# adapter.net
KiCad netlist of a schematic drawn in EAGLE
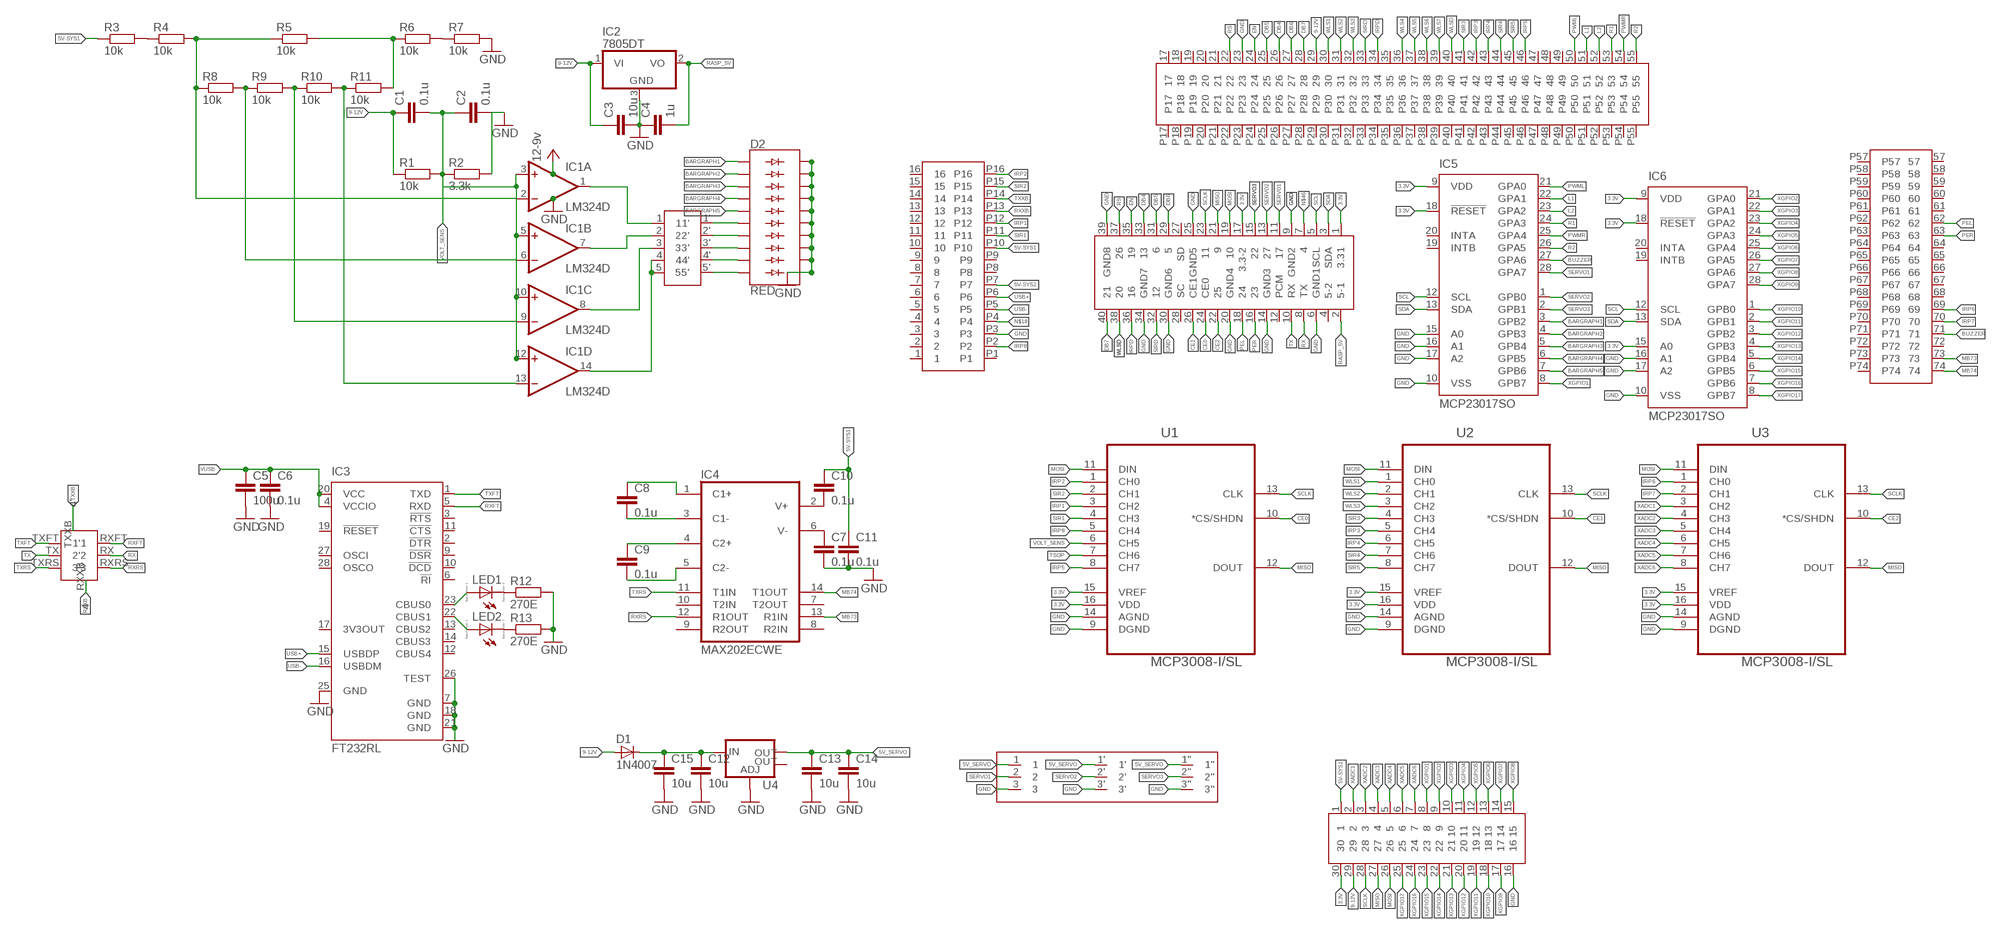
[diagram p0: schematic, sheet 1]

(export (version "E")
  (design (tool "Eeschema 10.0.6"))
  (components
    (comp (ref "C1")
      (value "0.1u")
      (footprint "eagle-import:C1206")
      (libsource (lib "eagle-import") (part "C-EUC1206"))
    )
    (comp (ref "C2")
      (value "0.1u")
      (footprint "eagle-import:C1206")
      (libsource (lib "eagle-import") (part "C-EUC1206"))
    )
    (comp (ref "C3")
      (value "10u")
      (footprint "eagle-import:C1206")
      (libsource (lib "eagle-import") (part "C-EUC1206"))
    )
    (comp (ref "C4")
      (value "1u")
      (footprint "eagle-import:C1206")
      (libsource (lib "eagle-import") (part "C-EUC1206"))
    )
    (comp (ref "C5")
      (value "100u")
      (footprint "eagle-import:C1206")
      (libsource (lib "eagle-import") (part "C-EUC1206"))
    )
    (comp (ref "C6")
      (value "0.1u")
      (footprint "eagle-import:C1206")
      (libsource (lib "eagle-import") (part "C-EUC1206"))
    )
    (comp (ref "C7")
      (value "0.1u")
      (footprint "eagle-import:C1206")
      (libsource (lib "eagle-import") (part "C-EUC1206"))
    )
    (comp (ref "C8")
      (value "0.1u")
      (footprint "eagle-import:C1206")
      (libsource (lib "eagle-import") (part "C-EUC1206"))
    )
    (comp (ref "C9")
      (value "0.1u")
      (footprint "eagle-import:C1206")
      (libsource (lib "eagle-import") (part "C-EUC1206"))
    )
    (comp (ref "C10")
      (value "0.1u")
      (footprint "eagle-import:C1206")
      (libsource (lib "eagle-import") (part "C-EUC1206"))
    )
    (comp (ref "C11")
      (value "0.1u")
      (footprint "eagle-import:C1206")
      (libsource (lib "eagle-import") (part "C-EUC1206"))
    )
    (comp (ref "C12")
      (value "10u")
      (footprint "eagle-import:C1206")
      (libsource (lib "eagle-import") (part "C-EUC1206"))
    )
    (comp (ref "C13")
      (value "10u")
      (footprint "eagle-import:C1206")
      (libsource (lib "eagle-import") (part "C-EUC1206"))
    )
    (comp (ref "C14")
      (value "10u")
      (footprint "eagle-import:C1206")
      (libsource (lib "eagle-import") (part "C-EUC1206"))
    )
    (comp (ref "C15")
      (value "10u")
      (footprint "eagle-import:C1206")
      (libsource (lib "eagle-import") (part "C-EUC1206"))
    )
    (comp (ref "D1")
      (value "1N4007")
      (footprint "eagle-import:SMA")
      (libsource (lib "eagle-import") (part "1N4007"))
    )
    (comp (ref "D2")
      (value "RED")
      (footprint "eagle-import:LED_BARGRAPH_10")
      (libsource (lib "eagle-import") (part "LED_BARGRAPH_10RED"))
    )
    (comp (ref "IC1")
      (value "LM324D")
      (footprint "eagle-import:SO14")
      (libsource (lib "eagle-import") (part "LM324D"))
    )
    (comp (ref "IC2")
      (value "7805DT")
      (footprint "eagle-import:TO252")
      (libsource (lib "eagle-import") (part "78DT05"))
    )
    (comp (ref "IC3")
      (value "FT232RL")
      (footprint "eagle-import:SSOP28")
      (libsource (lib "eagle-import") (part "FT232RL"))
    )
    (comp (ref "IC4")
      (value "MAX202ECWE")
      (footprint "eagle-import:SO16L")
      (fields (field (name "MPN") "MAX202ECWE+T"))
      (libsource (lib "eagle-import") (part "MAX202ECWE"))
    )
    (comp (ref "IC5")
      (value "MCP23017SO")
      (footprint "eagle-import:SO28W")
      (libsource (lib "eagle-import") (part "MCP23017SO"))
    )
    (comp (ref "IC6")
      (value "MCP23017SO")
      (footprint "eagle-import:SO28W")
      (libsource (lib "eagle-import") (part "MCP23017SO"))
    )
    (comp (ref "LED1")
      (value "LED_E")
      (footprint "eagle-import:LED_1206")
      (libsource (lib "eagle-import") (part "LED_E"))
    )
    (comp (ref "LED2")
      (value "LED_E")
      (footprint "eagle-import:LED_1206")
      (libsource (lib "eagle-import") (part "LED_E"))
    )
    (comp (ref "R1")
      (value "10k")
      (footprint "eagle-import:M1206")
      (libsource (lib "eagle-import") (part "R-EU_M1206"))
    )
    (comp (ref "R2")
      (value "3.3k")
      (footprint "eagle-import:M1206")
      (libsource (lib "eagle-import") (part "R-EU_M1206"))
    )
    (comp (ref "R3")
      (value "10k")
      (footprint "eagle-import:M1206")
      (libsource (lib "eagle-import") (part "R-EU_M1206"))
    )
    (comp (ref "R4")
      (value "10k")
      (footprint "eagle-import:M1206")
      (libsource (lib "eagle-import") (part "R-EU_M1206"))
    )
    (comp (ref "R5")
      (value "10k")
      (footprint "eagle-import:M1206")
      (libsource (lib "eagle-import") (part "R-EU_M1206"))
    )
    (comp (ref "R6")
      (value "10k")
      (footprint "eagle-import:M1206")
      (libsource (lib "eagle-import") (part "R-EU_M1206"))
    )
    (comp (ref "R7")
      (value "10k")
      (footprint "eagle-import:M1206")
      (libsource (lib "eagle-import") (part "R-EU_M1206"))
    )
    (comp (ref "R8")
      (value "10k")
      (footprint "eagle-import:M1206")
      (libsource (lib "eagle-import") (part "R-EU_M1206"))
    )
    (comp (ref "R9")
      (value "10k")
      (footprint "eagle-import:M1206")
      (libsource (lib "eagle-import") (part "R-EU_M1206"))
    )
    (comp (ref "R10")
      (value "10k")
      (footprint "eagle-import:M1206")
      (libsource (lib "eagle-import") (part "R-EU_M1206"))
    )
    (comp (ref "R11")
      (value "10k")
      (footprint "eagle-import:M1206")
      (libsource (lib "eagle-import") (part "R-EU_M1206"))
    )
    (comp (ref "R12")
      (value "270E")
      (footprint "eagle-import:R1206")
      (libsource (lib "eagle-import") (part "R-EU_R1206"))
    )
    (comp (ref "R13")
      (value "270E")
      (footprint "eagle-import:R1206")
      (libsource (lib "eagle-import") (part "R-EU_R1206"))
    )
    (comp (ref "U$1")
      (value "BOARD")
      (footprint "eagle-import:FEMHEADER")
      (libsource (lib "eagle-import") (part "BOARD"))
    )
    (comp (ref "U$2")
      (value "MALE_HEADER")
      (footprint "eagle-import:MALE_HEADER_PACKAGE")
      (libsource (lib "eagle-import") (part "MALE_HEADER"))
    )
    (comp (ref "U$3")
      (value "SWITCH_RXTX")
      (footprint "eagle-import:SWITCH_RXTX")
      (libsource (lib "eagle-import") (part "SWITCH_RXTX"))
    )
    (comp (ref "U$4")
      (value "SWITCH5")
      (footprint "eagle-import:SWITCH5")
      (libsource (lib "eagle-import") (part "SWITCH5"))
    )
    (comp (ref "U$5")
      (value "PORT_EXP")
      (footprint "eagle-import:PORT_EXP")
      (libsource (lib "eagle-import") (part "PORT_EXP"))
    )
    (comp (ref "U$7")
      (value "SERVO")
      (footprint "eagle-import:SERVO")
      (libsource (lib "eagle-import") (part "SERVO"))
    )
    (comp (ref "U1")
      (value "MCP3008-I/SL")
      (footprint "eagle-import:SOIC127P600X175-16N")
      (fields (field (name "MF") "Microchip"))
      (libsource (lib "eagle-import") (part "MCP3008-I/SL"))
    )
    (comp (ref "U2")
      (value "MCP3008-I/SL")
      (footprint "eagle-import:SOIC127P600X175-16N")
      (fields (field (name "MF") "Microchip"))
      (libsource (lib "eagle-import") (part "MCP3008-I/SL"))
    )
    (comp (ref "U3")
      (value "MCP3008-I/SL")
      (footprint "eagle-import:SOIC127P600X175-16N")
      (fields (field (name "MF") "Microchip"))
      (libsource (lib "eagle-import") (part "MCP3008-I/SL"))
    )
    (comp (ref "U4")
      (value "V_REG_LM1117SOT223")
      (footprint "eagle-import:SOT223")
      (libsource (lib "eagle-import") (part "V_REG_LM1117SOT223"))
    )
  )
  (nets
    (net (code "1") (name "3.3V") (class "Default")
      (node (ref "IC5") (pin "18") (pinfunction "~{RESET}_18") (pintype "input"))
      (node (ref "IC5") (pin "9") (pinfunction "VDD_9") (pintype "power_in"))
      (node (ref "IC6") (pin "15") (pinfunction "A0_15") (pintype "input"))
      (node (ref "IC6") (pin "18") (pinfunction "~{RESET}_18") (pintype "input"))
      (node (ref "IC6") (pin "9") (pinfunction "VDD_9") (pintype "power_in"))
      (node (ref "U$2") (pin "1") (pinfunction "3.31_1") (pintype "bidirectional"))
      (node (ref "U$2") (pin "17") (pinfunction "3.3-2_17") (pintype "bidirectional"))
      (node (ref "U$5") (pin "30") (pinfunction "30_30") (pintype "bidirectional"))
      (node (ref "U1") (pin "15") (pinfunction "VREF_15") (pintype "input"))
      (node (ref "U1") (pin "16") (pinfunction "VDD_16") (pintype "power_in"))
      (node (ref "U2") (pin "15") (pinfunction "VREF_15") (pintype "input"))
      (node (ref "U2") (pin "16") (pinfunction "VDD_16") (pintype "power_in"))
      (node (ref "U3") (pin "15") (pinfunction "VREF_15") (pintype "input"))
      (node (ref "U3") (pin "16") (pinfunction "VDD_16") (pintype "power_in"))
    )
    (net (code "2") (name "5V-SYS1") (class "Default")
      (node (ref "C10") (pin "1") (pinfunction "1_1") (pintype "passive"))
      (node (ref "C11") (pin "1") (pinfunction "1_1") (pintype "passive"))
      (node (ref "R3") (pin "1") (pinfunction "1_1") (pintype "passive"))
      (node (ref "U$1") (pin "P10") (pinfunction "P10_P10") (pintype "bidirectional"))
      (node (ref "U$5") (pin "1") (pinfunction "1_1") (pintype "bidirectional"))
    )
    (net (code "3") (name "5V-SYS2") (class "Default")
      (node (ref "U$1") (pin "P7") (pinfunction "P7_P7") (pintype "bidirectional"))
    )
    (net (code "4") (name "5V_SERVO") (class "Default")
      (node (ref "C13") (pin "1") (pinfunction "1_1") (pintype "passive"))
      (node (ref "C14") (pin "1") (pinfunction "1_1") (pintype "passive"))
      (node (ref "U$7") (pin "1") (pinfunction "1_1") (pintype "bidirectional"))
      (node (ref "U$7") (pin "1\"") (pinfunction "1\"_1\"") (pintype "bidirectional"))
      (node (ref "U$7") (pin "1'") (pinfunction "1'_1'") (pintype "bidirectional"))
      (node (ref "U4") (pin "2") (pinfunction "OUT_2") (pintype "output"))
    )
    (net (code "5") (name "9-12V") (class "Default")
      (node (ref "C1") (pin "1") (pinfunction "1_1") (pintype "passive"))
      (node (ref "C3") (pin "1") (pinfunction "1_1") (pintype "passive"))
      (node (ref "D1") (pin "A") (pinfunction "A_A") (pintype "passive"))
      (node (ref "IC2") (pin "1") (pinfunction "VI_1") (pintype "input"))
      (node (ref "R1") (pin "1") (pinfunction "1_1") (pintype "passive"))
      (node (ref "U$1") (pin "29") (pinfunction "29_29") (pintype "bidirectional"))
      (node (ref "U$5") (pin "29") (pinfunction "29_29") (pintype "bidirectional"))
    )
    (net (code "7") (name "BARGRAPH1") (class "Default")
      (node (ref "D2") (pin "1") (pinfunction "A_1") (pintype "passive"))
      (node (ref "IC5") (pin "3") (pinfunction "GPB2_3") (pintype "bidirectional"))
    )
    (net (code "8") (name "BARGRAPH2") (class "Default")
      (node (ref "D2") (pin "2") (pinfunction "A1_2") (pintype "passive"))
      (node (ref "IC5") (pin "4") (pinfunction "GPB3_4") (pintype "bidirectional"))
    )
    (net (code "9") (name "BARGRAPH3") (class "Default")
      (node (ref "D2") (pin "3") (pinfunction "A2_3") (pintype "passive"))
      (node (ref "IC5") (pin "5") (pinfunction "GPB4_5") (pintype "bidirectional"))
    )
    (net (code "10") (name "BARGRAPH4") (class "Default")
      (node (ref "D2") (pin "4") (pinfunction "A3_4") (pintype "passive"))
      (node (ref "IC5") (pin "6") (pinfunction "GPB5_6") (pintype "bidirectional"))
    )
    (net (code "11") (name "BARGRAPH5") (class "Default")
      (node (ref "D2") (pin "5") (pinfunction "A4_5") (pintype "passive"))
      (node (ref "IC5") (pin "7") (pinfunction "GPB6_7") (pintype "bidirectional"))
    )
    (net (code "12") (name "BUZZER") (class "Default")
      (node (ref "IC5") (pin "27") (pinfunction "GPA6_27") (pintype "bidirectional"))
      (node (ref "U$1") (pin "71") (pinfunction "71_71") (pintype "bidirectional"))
    )
    (net (code "13") (name "CE0") (class "Default")
      (node (ref "U$2") (pin "24") (pinfunction "CE0_24") (pintype "bidirectional"))
      (node (ref "U1") (pin "10") (pinfunction "*CS/SHDN_10") (pintype "input"))
    )
    (net (code "14") (name "CE1") (class "Default")
      (node (ref "U$2") (pin "26") (pinfunction "CE1_26") (pintype "bidirectional"))
      (node (ref "U2") (pin "10") (pinfunction "*CS/SHDN_10") (pintype "input"))
    )
    (net (code "15") (name "CE2") (class "Default")
      (node (ref "U$2") (pin "22") (pinfunction "25_22") (pintype "bidirectional"))
      (node (ref "U3") (pin "10") (pinfunction "*CS/SHDN_10") (pintype "input"))
    )
    (net (code "16") (name "DB4") (class "Default")
      (node (ref "U$1") (pin "26") (pinfunction "26_26") (pintype "bidirectional"))
      (node (ref "U$2") (pin "33") (pinfunction "13_33") (pintype "bidirectional"))
    )
    (net (code "17") (name "DB5") (class "Default")
      (node (ref "U$1") (pin "25") (pinfunction "25_25") (pintype "bidirectional"))
      (node (ref "U$2") (pin "31") (pinfunction "6_31") (pintype "bidirectional"))
    )
    (net (code "18") (name "DB6") (class "Default")
      (node (ref "U$1") (pin "27") (pinfunction "27_27") (pintype "bidirectional"))
      (node (ref "U$2") (pin "29") (pinfunction "5_29") (pintype "bidirectional"))
    )
    (net (code "19") (name "DB7") (class "Default")
      (node (ref "U$1") (pin "28") (pinfunction "28_28") (pintype "bidirectional"))
      (node (ref "U$2") (pin "40") (pinfunction "21_40") (pintype "bidirectional"))
    )
    (net (code "20") (name "EN") (class "Default")
      (node (ref "U$1") (pin "24") (pinfunction "24_24") (pintype "bidirectional"))
      (node (ref "U$2") (pin "35") (pinfunction "19_35") (pintype "bidirectional"))
    )
    (net (code "21") (name "GND") (class "Default")
      (node (ref "C11") (pin "2") (pinfunction "2_2") (pintype "passive"))
      (node (ref "C12") (pin "2") (pinfunction "2_2") (pintype "passive"))
      (node (ref "C13") (pin "2") (pinfunction "2_2") (pintype "passive"))
      (node (ref "C14") (pin "2") (pinfunction "2_2") (pintype "passive"))
      (node (ref "C15") (pin "2") (pinfunction "2_2") (pintype "passive"))
      (node (ref "C2") (pin "2") (pinfunction "2_2") (pintype "passive"))
      (node (ref "C3") (pin "2") (pinfunction "2_2") (pintype "passive"))
      (node (ref "C4") (pin "1") (pinfunction "1_1") (pintype "passive"))
      (node (ref "C5") (pin "2") (pinfunction "2_2") (pintype "passive"))
      (node (ref "C6") (pin "2") (pinfunction "2_2") (pintype "passive"))
      (node (ref "C7") (pin "2") (pinfunction "2_2") (pintype "passive"))
      (node (ref "D2") (pin "11") (pinfunction "C9_11") (pintype "passive"))
      (node (ref "D2") (pin "12") (pinfunction "C8_12") (pintype "passive"))
      (node (ref "D2") (pin "13") (pinfunction "C7_13") (pintype "passive"))
      (node (ref "D2") (pin "14") (pinfunction "C6_14") (pintype "passive"))
      (node (ref "D2") (pin "15") (pinfunction "C5_15") (pintype "passive"))
      (node (ref "D2") (pin "16") (pinfunction "C4_16") (pintype "passive"))
      (node (ref "D2") (pin "17") (pinfunction "C3_17") (pintype "passive"))
      (node (ref "D2") (pin "18") (pinfunction "C2_18") (pintype "passive"))
      (node (ref "D2") (pin "19") (pinfunction "C1_19") (pintype "passive"))
      (node (ref "D2") (pin "20") (pinfunction "C_20") (pintype "passive"))
      (node (ref "IC2") (pin "3") (pinfunction "GND_3") (pintype "passive"))
      (node (ref "IC3") (pin "18") (pinfunction "GND_18") (pintype "power_in"))
      (node (ref "IC3") (pin "21") (pinfunction "GND_21") (pintype "power_in"))
      (node (ref "IC3") (pin "25") (pinfunction "GND_25") (pintype "power_in"))
      (node (ref "IC3") (pin "26") (pinfunction "TEST_26") (pintype "input"))
      (node (ref "IC3") (pin "7") (pinfunction "GND_7") (pintype "power_in"))
      (node (ref "IC5") (pin "10") (pinfunction "VSS_10") (pintype "power_in"))
      (node (ref "IC5") (pin "15") (pinfunction "A0_15") (pintype "input"))
      (node (ref "IC5") (pin "16") (pinfunction "A1_16") (pintype "input"))
      (node (ref "IC5") (pin "17") (pinfunction "A2_17") (pintype "input"))
      (node (ref "IC6") (pin "10") (pinfunction "VSS_10") (pintype "power_in"))
      (node (ref "IC6") (pin "16") (pinfunction "A1_16") (pintype "input"))
      (node (ref "IC6") (pin "17") (pinfunction "A2_17") (pintype "input"))
      (node (ref "R12") (pin "2") (pinfunction "2_2") (pintype "passive"))
      (node (ref "R13") (pin "2") (pinfunction "2_2") (pintype "passive"))
      (node (ref "R2") (pin "2") (pinfunction "2_2") (pintype "passive"))
      (node (ref "R7") (pin "2") (pinfunction "2_2") (pintype "passive"))
      (node (ref "U$1") (pin "23") (pinfunction "23_23") (pintype "bidirectional"))
      (node (ref "U$1") (pin "P3") (pinfunction "P3_P3") (pintype "bidirectional"))
      (node (ref "U$2") (pin "14") (pinfunction "GND3_14") (pintype "bidirectional"))
      (node (ref "U$2") (pin "20") (pinfunction "GND4_20") (pintype "bidirectional"))
      (node (ref "U$2") (pin "25") (pinfunction "GND5_25") (pintype "bidirectional"))
      (node (ref "U$2") (pin "30") (pinfunction "GND6_30") (pintype "bidirectional"))
      (node (ref "U$2") (pin "34") (pinfunction "GND7_34") (pintype "bidirectional"))
      (node (ref "U$2") (pin "39") (pinfunction "GND8_39") (pintype "bidirectional"))
      (node (ref "U$2") (pin "6") (pinfunction "GND1_6") (pintype "bidirectional"))
      (node (ref "U$2") (pin "9") (pinfunction "GND2_9") (pintype "bidirectional"))
      (node (ref "U$5") (pin "16") (pinfunction "16_16") (pintype "bidirectional"))
      (node (ref "U$7") (pin "3") (pinfunction "3_3") (pintype "bidirectional"))
      (node (ref "U$7") (pin "3\"") (pinfunction "3\"_3\"") (pintype "bidirectional"))
      (node (ref "U$7") (pin "3'") (pinfunction "3'_3'") (pintype "bidirectional"))
      (node (ref "U1") (pin "14") (pinfunction "AGND_14") (pintype "passive"))
      (node (ref "U1") (pin "9") (pinfunction "DGND_9") (pintype "passive"))
      (node (ref "U2") (pin "14") (pinfunction "AGND_14") (pintype "passive"))
      (node (ref "U2") (pin "9") (pinfunction "DGND_9") (pintype "passive"))
      (node (ref "U3") (pin "14") (pinfunction "AGND_14") (pintype "passive"))
      (node (ref "U3") (pin "9") (pinfunction "DGND_9") (pintype "passive"))
      (node (ref "U4") (pin "1") (pinfunction "ADJ_1") (pintype "input"))
    )
    (net (code "22") (name "IRP1") (class "Default")
      (node (ref "U$1") (pin "P12") (pinfunction "P12_P12") (pintype "bidirectional"))
      (node (ref "U1") (pin "3") (pinfunction "CH2_3") (pintype "input"))
    )
    (net (code "23") (name "IRP2") (class "Default")
      (node (ref "U$1") (pin "P16") (pinfunction "P16_P16") (pintype "bidirectional"))
      (node (ref "U1") (pin "1") (pinfunction "CH0_1") (pintype "input"))
    )
    (net (code "24") (name "IRP3") (class "Default")
      (node (ref "U$1") (pin "42") (pinfunction "42_42") (pintype "bidirectional"))
      (node (ref "U2") (pin "5") (pinfunction "CH4_5") (pintype "input"))
    )
    (net (code "25") (name "IRP4") (class "Default")
      (node (ref "U$1") (pin "43") (pinfunction "43_43") (pintype "bidirectional"))
      (node (ref "U2") (pin "6") (pinfunction "CH5_6") (pintype "input"))
    )
    (net (code "26") (name "IRP5") (class "Default")
      (node (ref "U$1") (pin "46") (pinfunction "46_46") (pintype "bidirectional"))
      (node (ref "U1") (pin "8") (pinfunction "CH7_8") (pintype "input"))
    )
    (net (code "27") (name "IRP6") (class "Default")
      (node (ref "U$1") (pin "69") (pinfunction "69_69") (pintype "bidirectional"))
      (node (ref "U3") (pin "1") (pinfunction "CH0_1") (pintype "input"))
    )
    (net (code "28") (name "IRP7") (class "Default")
      (node (ref "U$1") (pin "70") (pinfunction "70_70") (pintype "bidirectional"))
      (node (ref "U3") (pin "2") (pinfunction "CH1_2") (pintype "input"))
    )
    (net (code "29") (name "IRP8") (class "Default")
      (node (ref "U$1") (pin "P2") (pinfunction "P2_P2") (pintype "bidirectional"))
      (node (ref "U1") (pin "5") (pinfunction "CH4_5") (pintype "input"))
    )
    (net (code "30") (name "IRPD") (class "Default")
      (node (ref "U$1") (pin "34") (pinfunction "34_34") (pintype "bidirectional"))
      (node (ref "U$2") (pin "36") (pinfunction "16_36") (pintype "bidirectional"))
    )
    (net (code "31") (name "L1") (class "Default")
      (node (ref "IC5") (pin "22") (pinfunction "GPA1_22") (pintype "bidirectional"))
      (node (ref "U$1") (pin "51") (pinfunction "51_51") (pintype "bidirectional"))
    )
    (net (code "32") (name "L2") (class "Default")
      (node (ref "IC5") (pin "23") (pinfunction "GPA2_23") (pintype "bidirectional"))
      (node (ref "U$1") (pin "52") (pinfunction "52_52") (pintype "bidirectional"))
    )
    (net (code "33") (name "MB73") (class "Default")
      (node (ref "IC4") (pin "13") (pinfunction "R1IN_13") (pintype "input"))
      (node (ref "U$1") (pin "73") (pinfunction "73_73") (pintype "bidirectional"))
    )
    (net (code "34") (name "MB74") (class "Default")
      (node (ref "IC4") (pin "14") (pinfunction "T1OUT_14") (pintype "output"))
      (node (ref "U$1") (pin "74") (pinfunction "74_74") (pintype "bidirectional"))
    )
    (net (code "35") (name "MISO") (class "Default")
      (node (ref "U$2") (pin "21") (pinfunction "9_21") (pintype "bidirectional"))
      (node (ref "U$5") (pin "27") (pinfunction "27_27") (pintype "bidirectional"))
      (node (ref "U1") (pin "12") (pinfunction "DOUT_12") (pintype "output"))
      (node (ref "U2") (pin "12") (pinfunction "DOUT_12") (pintype "output"))
      (node (ref "U3") (pin "12") (pinfunction "DOUT_12") (pintype "output"))
    )
    (net (code "36") (name "MOSI") (class "Default")
      (node (ref "U$2") (pin "19") (pinfunction "10_19") (pintype "bidirectional"))
      (node (ref "U$5") (pin "26") (pinfunction "26_26") (pintype "bidirectional"))
      (node (ref "U1") (pin "11") (pinfunction "DIN_11") (pintype "input"))
      (node (ref "U2") (pin "11") (pinfunction "DIN_11") (pintype "input"))
      (node (ref "U3") (pin "11") (pinfunction "DIN_11") (pintype "input"))
    )
    (net (code "37") (name "N$18") (class "Default")
      (node (ref "U$1") (pin "P4") (pinfunction "P4_P4") (pintype "bidirectional"))
    )
    (net (code "38") (name "N$46") (class "Default")
      (node (ref "U$2") (pin "7") (pinfunction "4_7") (pintype "bidirectional"))
    )
    (net (code "39") (name "Net-(D1-C)") (class "Default")
      (node (ref "C12") (pin "1") (pinfunction "1_1") (pintype "passive"))
      (node (ref "C15") (pin "1") (pinfunction "1_1") (pintype "passive"))
      (node (ref "D1") (pin "K") (pinfunction "C_K") (pintype "passive"))
      (node (ref "U4") (pin "3") (pinfunction "IN_3") (pintype "input"))
    )
    (net (code "40") (name "Net-(D2-A5)") (class "Default")
      (node (ref "D2") (pin "6") (pinfunction "A5_6") (pintype "passive"))
      (node (ref "U$4") (pin "1'") (pinfunction "1'_1'") (pintype "bidirectional"))
    )
    (net (code "41") (name "Net-(D2-A6)") (class "Default")
      (node (ref "D2") (pin "7") (pinfunction "A6_7") (pintype "passive"))
      (node (ref "U$4") (pin "2'") (pinfunction "2'_2'") (pintype "bidirectional"))
    )
    (net (code "42") (name "Net-(D2-A7)") (class "Default")
      (node (ref "D2") (pin "8") (pinfunction "A7_8") (pintype "passive"))
      (node (ref "U$4") (pin "3'") (pinfunction "3'_3'") (pintype "bidirectional"))
    )
    (net (code "43") (name "Net-(D2-A8)") (class "Default")
      (node (ref "D2") (pin "9") (pinfunction "A8_9") (pintype "passive"))
      (node (ref "U$4") (pin "4'") (pinfunction "4'_4'") (pintype "bidirectional"))
    )
    (net (code "44") (name "Net-(D2-A9)") (class "Default")
      (node (ref "D2") (pin "10") (pinfunction "A9_10") (pintype "passive"))
      (node (ref "U$4") (pin "5'") (pinfunction "5'_5'") (pintype "bidirectional"))
    )
    (net (code "45") (name "Net-(IC1A--IN)") (class "Default")
      (node (ref "IC1") (pin "2") (pinfunction "-IN_2") (pintype "input"))
      (node (ref "R4") (pin "2") (pinfunction "2_2") (pintype "passive"))
      (node (ref "R5") (pin "1") (pinfunction "1_1") (pintype "passive"))
      (node (ref "R8") (pin "1") (pinfunction "1_1") (pintype "passive"))
    )
    (net (code "46") (name "Net-(IC1A-OUT)") (class "Default")
      (node (ref "IC1") (pin "1") (pinfunction "OUT_1") (pintype "output"))
      (node (ref "U$4") (pin "1") (pinfunction "1_1") (pintype "bidirectional"))
    )
    (net (code "47") (name "Net-(IC1B--IN)") (class "Default")
      (node (ref "IC1") (pin "6") (pinfunction "-IN_6") (pintype "input"))
      (node (ref "R8") (pin "2") (pinfunction "2_2") (pintype "passive"))
      (node (ref "R9") (pin "1") (pinfunction "1_1") (pintype "passive"))
    )
    (net (code "48") (name "Net-(IC1B-OUT)") (class "Default")
      (node (ref "IC1") (pin "7") (pinfunction "OUT_7") (pintype "output"))
      (node (ref "U$4") (pin "2") (pinfunction "2_2") (pintype "bidirectional"))
    )
    (net (code "49") (name "Net-(IC1C--IN)") (class "Default")
      (node (ref "IC1") (pin "9") (pinfunction "-IN_9") (pintype "input"))
      (node (ref "R10") (pin "1") (pinfunction "1_1") (pintype "passive"))
      (node (ref "R9") (pin "2") (pinfunction "2_2") (pintype "passive"))
    )
    (net (code "50") (name "Net-(IC1C-OUT)") (class "Default")
      (node (ref "IC1") (pin "8") (pinfunction "OUT_8") (pintype "output"))
      (node (ref "U$4") (pin "3") (pinfunction "3_3") (pintype "bidirectional"))
    )
    (net (code "51") (name "Net-(IC1D--IN)") (class "Default")
      (node (ref "IC1") (pin "13") (pinfunction "-IN_13") (pintype "input"))
      (node (ref "R10") (pin "2") (pinfunction "2_2") (pintype "passive"))
      (node (ref "R11") (pin "1") (pinfunction "1_1") (pintype "passive"))
    )
    (net (code "52") (name "Net-(IC1D-OUT)") (class "Default")
      (node (ref "IC1") (pin "14") (pinfunction "OUT_14") (pintype "output"))
      (node (ref "U$4") (pin "4") (pinfunction "4_4") (pintype "bidirectional"))
      (node (ref "U$4") (pin "5") (pinfunction "5_5") (pintype "bidirectional"))
    )
    (net (code "53") (name "Net-(IC3-CBUS0)") (class "Default")
      (node (ref "IC3") (pin "23") (pinfunction "CBUS0_23") (pintype "bidirectional"))
      (node (ref "LED1") (pin "A") (pinfunction "A_A") (pintype "passive"))
    )
    (net (code "54") (name "Net-(IC3-CBUS1)") (class "Default")
      (node (ref "IC3") (pin "22") (pinfunction "CBUS1_22") (pintype "bidirectional"))
      (node (ref "LED2") (pin "A") (pinfunction "A_A") (pintype "passive"))
    )
    (net (code "55") (name "Net-(IC4A-C1+)") (class "Default")
      (node (ref "C8") (pin "1") (pinfunction "1_1") (pintype "passive"))
      (node (ref "IC4") (pin "1") (pinfunction "C1+_1") (pintype "bidirectional"))
    )
    (net (code "56") (name "Net-(IC4A-C1-)") (class "Default")
      (node (ref "C8") (pin "2") (pinfunction "2_2") (pintype "passive"))
      (node (ref "IC4") (pin "3") (pinfunction "C1-_3") (pintype "bidirectional"))
    )
    (net (code "57") (name "Net-(IC4A-C2+)") (class "Default")
      (node (ref "C9") (pin "1") (pinfunction "1_1") (pintype "passive"))
      (node (ref "IC4") (pin "4") (pinfunction "C2+_4") (pintype "bidirectional"))
    )
    (net (code "58") (name "Net-(IC4A-C2-)") (class "Default")
      (node (ref "C9") (pin "2") (pinfunction "2_2") (pintype "passive"))
      (node (ref "IC4") (pin "5") (pinfunction "C2-_5") (pintype "bidirectional"))
    )
    (net (code "59") (name "Net-(IC4A-V+)") (class "Default")
      (node (ref "C10") (pin "2") (pinfunction "2_2") (pintype "passive"))
      (node (ref "IC4") (pin "2") (pinfunction "V+_2") (pintype "bidirectional"))
    )
    (net (code "60") (name "Net-(IC4A-V-)") (class "Default")
      (node (ref "C7") (pin "1") (pinfunction "1_1") (pintype "passive"))
      (node (ref "IC4") (pin "6") (pinfunction "V-_6") (pintype "bidirectional"))
    )
    (net (code "61") (name "Net-(LED1-PadC)") (class "Default")
      (node (ref "LED1") (pin "C") (pinfunction "C_C") (pintype "passive"))
      (node (ref "R12") (pin "1") (pinfunction "1_1") (pintype "passive"))
    )
    (net (code "62") (name "Net-(LED2-PadC)") (class "Default")
      (node (ref "LED2") (pin "C") (pinfunction "C_C") (pintype "passive"))
      (node (ref "R13") (pin "1") (pinfunction "1_1") (pintype "passive"))
    )
    (net (code "63") (name "Net-(R3-Pad2)") (class "Default")
      (node (ref "R3") (pin "2") (pinfunction "2_2") (pintype "passive"))
      (node (ref "R4") (pin "1") (pinfunction "1_1") (pintype "passive"))
    )
    (net (code "64") (name "Net-(R6-Pad2)") (class "Default")
      (node (ref "R6") (pin "2") (pinfunction "2_2") (pintype "passive"))
      (node (ref "R7") (pin "1") (pinfunction "1_1") (pintype "passive"))
    )
    (net (code "65") (name "Net-(R11-Pad2)") (class "Default")
      (node (ref "R11") (pin "2") (pinfunction "2_2") (pintype "passive"))
      (node (ref "R5") (pin "2") (pinfunction "2_2") (pintype "passive"))
      (node (ref "R6") (pin "1") (pinfunction "1_1") (pintype "passive"))
    )
    (net (code "66") (name "PEL") (class "Default")
      (node (ref "U$1") (pin "62") (pinfunction "62_62") (pintype "bidirectional"))
      (node (ref "U$2") (pin "18") (pinfunction "24_18") (pintype "bidirectional"))
    )
    (net (code "67") (name "PER") (class "Default")
      (node (ref "U$1") (pin "63") (pinfunction "63_63") (pintype "bidirectional"))
      (node (ref "U$2") (pin "16") (pinfunction "23_16") (pintype "bidirectional"))
    )
    (net (code "68") (name "PWML") (class "Default")
      (node (ref "IC5") (pin "21") (pinfunction "GPA0_21") (pintype "bidirectional"))
      (node (ref "U$1") (pin "50") (pinfunction "50_50") (pintype "bidirectional"))
    )
    (net (code "69") (name "PWMR") (class "Default")
      (node (ref "IC5") (pin "25") (pinfunction "GPA4_25") (pintype "bidirectional"))
      (node (ref "U$1") (pin "54") (pinfunction "54_54") (pintype "bidirectional"))
    )
    (net (code "70") (name "R1") (class "Default")
      (node (ref "IC5") (pin "24") (pinfunction "GPA3_24") (pintype "bidirectional"))
      (node (ref "U$1") (pin "53") (pinfunction "53_53") (pintype "bidirectional"))
    )
    (net (code "71") (name "R2") (class "Default")
      (node (ref "IC5") (pin "26") (pinfunction "GPA5_26") (pintype "bidirectional"))
      (node (ref "U$1") (pin "55") (pinfunction "55_55") (pintype "bidirectional"))
    )
    (net (code "72") (name "RASP_5V") (class "Default")
      (node (ref "C4") (pin "2") (pinfunction "2_2") (pintype "passive"))
      (node (ref "IC2") (pin "2") (pinfunction "VO_2") (pintype "passive"))
      (node (ref "U$2") (pin "2") (pinfunction "5-1_2") (pintype "bidirectional"))
    )
    (net (code "73") (name "RS") (class "Default")
      (node (ref "U$1") (pin "22") (pinfunction "22_22") (pintype "bidirectional"))
      (node (ref "U$2") (pin "37") (pinfunction "26_37") (pintype "bidirectional"))
    )
    (net (code "74") (name "RX") (class "Default")
      (node (ref "U$2") (pin "8") (pinfunction "TX_8") (pintype "bidirectional"))
      (node (ref "U$3") (pin "RX") (pinfunction "2_RX") (pintype "bidirectional"))
    )
    (net (code "75") (name "RXFT") (class "Default")
      (node (ref "IC3") (pin "5") (pinfunction "RXD_5") (pintype "input"))
      (node (ref "U$3") (pin "RXFT") (pinfunction "1_RXFT") (pintype "bidirectional"))
    )
    (net (code "76") (name "RXRS") (class "Default")
      (node (ref "IC4") (pin "12") (pinfunction "R1OUT_12") (pintype "output"))
      (node (ref "U$3") (pin "RXRS") (pinfunction "3_RXRS") (pintype "bidirectional"))
    )
    (net (code "77") (name "RXXB") (class "Default")
      (node (ref "U$1") (pin "P13") (pinfunction "P13_P13") (pintype "bidirectional"))
      (node (ref "U$3") (pin "RXXB") (pinfunction "4_RXXB") (pintype "bidirectional"))
    )
    (net (code "78") (name "SCL") (class "Default")
      (node (ref "IC5") (pin "12") (pinfunction "SCL_12") (pintype "input"))
      (node (ref "IC6") (pin "12") (pinfunction "SCL_12") (pintype "input"))
      (node (ref "U$2") (pin "5") (pinfunction "SCL_5") (pintype "bidirectional"))
    )
    (net (code "79") (name "SCLK") (class "Default")
      (node (ref "U$2") (pin "23") (pinfunction "11_23") (pintype "bidirectional"))
      (node (ref "U$5") (pin "28") (pinfunction "28_28") (pintype "bidirectional"))
      (node (ref "U1") (pin "13") (pinfunction "CLK_13") (pintype "input"))
      (node (ref "U2") (pin "13") (pinfunction "CLK_13") (pintype "input"))
      (node (ref "U3") (pin "13") (pinfunction "CLK_13") (pintype "input"))
    )
    (net (code "80") (name "SDA") (class "Default")
      (node (ref "IC5") (pin "13") (pinfunction "SDA_13") (pintype "bidirectional"))
      (node (ref "IC6") (pin "13") (pinfunction "SDA_13") (pintype "bidirectional"))
      (node (ref "U$2") (pin "3") (pinfunction "SDA_3") (pintype "bidirectional"))
    )
    (net (code "81") (name "SERVO1") (class "Default")
      (node (ref "IC5") (pin "28") (pinfunction "GPA7_28") (pintype "bidirectional"))
      (node (ref "U$2") (pin "11") (pinfunction "17_11") (pintype "bidirectional"))
      (node (ref "U$7") (pin "2") (pinfunction "2_2") (pintype "bidirectional"))
    )
    (net (code "82") (name "SERVO2") (class "Default")
      (node (ref "IC5") (pin "1") (pinfunction "GPB0_1") (pintype "bidirectional"))
      (node (ref "U$2") (pin "13") (pinfunction "27_13") (pintype "bidirectional"))
      (node (ref "U$7") (pin "2'") (pinfunction "2'_2'") (pintype "bidirectional"))
    )
    (net (code "83") (name "SERVO3") (class "Default")
      (node (ref "IC5") (pin "2") (pinfunction "GPB1_2") (pintype "bidirectional"))
      (node (ref "U$2") (pin "15") (pinfunction "22_15") (pintype "bidirectional"))
      (node (ref "U$7") (pin "2\"") (pinfunction "2\"_2\"") (pintype "bidirectional"))
    )
    (net (code "84") (name "SIR1") (class "Default")
      (node (ref "U$1") (pin "P11") (pinfunction "P11_P11") (pintype "bidirectional"))
      (node (ref "U1") (pin "4") (pinfunction "CH3_4") (pintype "input"))
    )
    (net (code "85") (name "SIR2") (class "Default")
      (node (ref "U$1") (pin "P15") (pinfunction "P15_P15") (pintype "bidirectional"))
      (node (ref "U1") (pin "2") (pinfunction "CH1_2") (pintype "input"))
    )
    (net (code "86") (name "SIR3") (class "Default")
      (node (ref "U$1") (pin "41") (pinfunction "41_41") (pintype "bidirectional"))
      (node (ref "U2") (pin "4") (pinfunction "CH3_4") (pintype "input"))
    )
    (net (code "87") (name "SIR4") (class "Default")
      (node (ref "U$1") (pin "44") (pinfunction "44_44") (pintype "bidirectional"))
      (node (ref "U2") (pin "7") (pinfunction "CH6_7") (pintype "input"))
    )
    (net (code "88") (name "SIR5") (class "Default")
      (node (ref "U$1") (pin "45") (pinfunction "45_45") (pintype "bidirectional"))
      (node (ref "U2") (pin "8") (pinfunction "CH7_8") (pintype "input"))
    )
    (net (code "89") (name "SIRD") (class "Default")
      (node (ref "U$1") (pin "33") (pinfunction "33_33") (pintype "bidirectional"))
      (node (ref "U$2") (pin "32") (pinfunction "12_32") (pintype "bidirectional"))
    )
    (net (code "90") (name "TSOP") (class "Default")
      (node (ref "U1") (pin "7") (pinfunction "CH6_7") (pintype "input"))
    )
    (net (code "91") (name "TX") (class "Default")
      (node (ref "U$2") (pin "10") (pinfunction "RX_10") (pintype "bidirectional"))
      (node (ref "U$3") (pin "TX") (pinfunction "2'_TX") (pintype "bidirectional"))
    )
    (net (code "92") (name "TXFT") (class "Default")
      (node (ref "IC3") (pin "1") (pinfunction "TXD_1") (pintype "output"))
      (node (ref "U$3") (pin "TXFT") (pinfunction "1'_TXFT") (pintype "bidirectional"))
    )
    (net (code "93") (name "TXRS") (class "Default")
      (node (ref "IC4") (pin "11") (pinfunction "T1IN_11") (pintype "input"))
      (node (ref "U$3") (pin "TXRS") (pinfunction "3'_TXRS") (pintype "bidirectional"))
    )
    (net (code "94") (name "TXXB") (class "Default")
      (node (ref "U$1") (pin "P14") (pinfunction "P14_P14") (pintype "bidirectional"))
      (node (ref "U$3") (pin "TXXB") (pinfunction "4'_TXXB") (pintype "bidirectional"))
    )
    (net (code "95") (name "USB+") (class "Default")
      (node (ref "IC3") (pin "15") (pinfunction "USBDP_15") (pintype "bidirectional"))
      (node (ref "U$1") (pin "P6") (pinfunction "P6_P6") (pintype "bidirectional"))
    )
    (net (code "96") (name "USB-") (class "Default")
      (node (ref "IC3") (pin "16") (pinfunction "USBDM_16") (pintype "bidirectional"))
      (node (ref "U$1") (pin "P5") (pinfunction "P5_P5") (pintype "bidirectional"))
    )
    (net (code "97") (name "VOLT_SENS") (class "Default")
      (node (ref "C1") (pin "2") (pinfunction "2_2") (pintype "passive"))
      (node (ref "C2") (pin "1") (pinfunction "1_1") (pintype "passive"))
      (node (ref "IC1") (pin "10") (pinfunction "+IN_10") (pintype "input"))
      (node (ref "IC1") (pin "12") (pinfunction "+IN_12") (pintype "input"))
      (node (ref "IC1") (pin "3") (pinfunction "+IN_3") (pintype "input"))
      (node (ref "IC1") (pin "5") (pinfunction "+IN_5") (pintype "input"))
      (node (ref "R1") (pin "2") (pinfunction "2_2") (pintype "passive"))
      (node (ref "R2") (pin "1") (pinfunction "1_1") (pintype "passive"))
      (node (ref "U1") (pin "6") (pinfunction "CH5_6") (pintype "input"))
    )
    (net (code "98") (name "VUSB") (class "Default")
      (node (ref "C5") (pin "1") (pinfunction "1_1") (pintype "passive"))
      (node (ref "C6") (pin "1") (pinfunction "1_1") (pintype "passive"))
      (node (ref "IC3") (pin "20") (pinfunction "VCC_20") (pintype "power_in"))
      (node (ref "IC3") (pin "4") (pinfunction "VCCIO_4") (pintype "power_in"))
    )
    (net (code "99") (name "WLS1") (class "Default")
      (node (ref "U$1") (pin "30") (pinfunction "30_30") (pintype "bidirectional"))
      (node (ref "U2") (pin "1") (pinfunction "CH0_1") (pintype "input"))
    )
    (net (code "100") (name "WLS2") (class "Default")
      (node (ref "U$1") (pin "31") (pinfunction "31_31") (pintype "bidirectional"))
      (node (ref "U2") (pin "2") (pinfunction "CH1_2") (pintype "input"))
    )
    (net (code "101") (name "WLS3") (class "Default")
      (node (ref "U$1") (pin "32") (pinfunction "32_32") (pintype "bidirectional"))
      (node (ref "U2") (pin "3") (pinfunction "CH2_3") (pintype "input"))
    )
    (net (code "102") (name "WLS4") (class "Default")
      (node (ref "U$1") (pin "36") (pinfunction "36_36") (pintype "bidirectional"))
    )
    (net (code "103") (name "WLS5") (class "Default")
      (node (ref "U$1") (pin "37") (pinfunction "37_37") (pintype "bidirectional"))
    )
    (net (code "104") (name "WLS6") (class "Default")
      (node (ref "U$1") (pin "38") (pinfunction "38_38") (pintype "bidirectional"))
    )
    (net (code "105") (name "WLS7") (class "Default")
      (node (ref "U$1") (pin "39") (pinfunction "39_39") (pintype "bidirectional"))
    )
    (net (code "106") (name "WLSD") (class "Default")
      (node (ref "U$1") (pin "40") (pinfunction "40_40") (pintype "bidirectional"))
      (node (ref "U$2") (pin "38") (pinfunction "20_38") (pintype "bidirectional"))
    )
    (net (code "107") (name "XADC1") (class "Default")
      (node (ref "U$5") (pin "2") (pinfunction "2_2") (pintype "bidirectional"))
      (node (ref "U3") (pin "3") (pinfunction "CH2_3") (pintype "input"))
    )
    (net (code "108") (name "XADC2") (class "Default")
      (node (ref "U$5") (pin "3") (pinfunction "3_3") (pintype "bidirectional"))
      (node (ref "U3") (pin "4") (pinfunction "CH3_4") (pintype "input"))
    )
    (net (code "109") (name "XADC3") (class "Default")
      (node (ref "U$5") (pin "4") (pinfunction "4_4") (pintype "bidirectional"))
      (node (ref "U3") (pin "5") (pinfunction "CH4_5") (pintype "input"))
    )
    (net (code "110") (name "XADC4") (class "Default")
      (node (ref "U$5") (pin "5") (pinfunction "5_5") (pintype "bidirectional"))
      (node (ref "U3") (pin "6") (pinfunction "CH5_6") (pintype "input"))
    )
    (net (code "111") (name "XADC5") (class "Default")
      (node (ref "U$5") (pin "6") (pinfunction "6_6") (pintype "bidirectional"))
      (node (ref "U3") (pin "7") (pinfunction "CH6_7") (pintype "input"))
    )
    (net (code "112") (name "XADC6") (class "Default")
      (node (ref "U$5") (pin "7") (pinfunction "7_7") (pintype "bidirectional"))
      (node (ref "U3") (pin "8") (pinfunction "CH7_8") (pintype "input"))
    )
    (net (code "113") (name "XGPIO1") (class "Default")
      (node (ref "IC5") (pin "8") (pinfunction "GPB7_8") (pintype "bidirectional"))
      (node (ref "U$5") (pin "8") (pinfunction "8_8") (pintype "bidirectional"))
    )
    (net (code "114") (name "XGPIO2") (class "Default")
      (node (ref "IC6") (pin "21") (pinfunction "GPA0_21") (pintype "bidirectional"))
      (node (ref "U$5") (pin "9") (pinfunction "9_9") (pintype "bidirectional"))
    )
    (net (code "115") (name "XGPIO3") (class "Default")
      (node (ref "IC6") (pin "22") (pinfunction "GPA1_22") (pintype "bidirectional"))
      (node (ref "U$5") (pin "10") (pinfunction "10_10") (pintype "bidirectional"))
    )
    (net (code "116") (name "XGPIO4") (class "Default")
      (node (ref "IC6") (pin "23") (pinfunction "GPA2_23") (pintype "bidirectional"))
      (node (ref "U$5") (pin "11") (pinfunction "11_11") (pintype "bidirectional"))
    )
    (net (code "117") (name "XGPIO5") (class "Default")
      (node (ref "IC6") (pin "24") (pinfunction "GPA3_24") (pintype "bidirectional"))
      (node (ref "U$5") (pin "12") (pinfunction "12_12") (pintype "bidirectional"))
    )
    (net (code "118") (name "XGPIO6") (class "Default")
      (node (ref "IC6") (pin "25") (pinfunction "GPA4_25") (pintype "bidirectional"))
      (node (ref "U$5") (pin "13") (pinfunction "13_13") (pintype "bidirectional"))
    )
    (net (code "119") (name "XGPIO7") (class "Default")
      (node (ref "IC6") (pin "26") (pinfunction "GPA5_26") (pintype "bidirectional"))
      (node (ref "U$5") (pin "14") (pinfunction "14_14") (pintype "bidirectional"))
    )
    (net (code "120") (name "XGPIO8") (class "Default")
      (node (ref "IC6") (pin "27") (pinfunction "GPA6_27") (pintype "bidirectional"))
      (node (ref "U$5") (pin "15") (pinfunction "15_15") (pintype "bidirectional"))
    )
    (net (code "121") (name "XGPIO9") (class "Default")
      (node (ref "IC6") (pin "28") (pinfunction "GPA7_28") (pintype "bidirectional"))
      (node (ref "U$5") (pin "17") (pinfunction "17_17") (pintype "bidirectional"))
    )
    (net (code "122") (name "XGPIO10") (class "Default")
      (node (ref "IC6") (pin "1") (pinfunction "GPB0_1") (pintype "bidirectional"))
      (node (ref "U$5") (pin "18") (pinfunction "18_18") (pintype "bidirectional"))
    )
    (net (code "123") (name "XGPIO11") (class "Default")
      (node (ref "IC6") (pin "2") (pinfunction "GPB1_2") (pintype "bidirectional"))
      (node (ref "U$5") (pin "19") (pinfunction "19_19") (pintype "bidirectional"))
    )
    (net (code "124") (name "XGPIO12") (class "Default")
      (node (ref "IC6") (pin "3") (pinfunction "GPB2_3") (pintype "bidirectional"))
      (node (ref "U$5") (pin "20") (pinfunction "20_20") (pintype "bidirectional"))
    )
    (net (code "125") (name "XGPIO13") (class "Default")
      (node (ref "IC6") (pin "4") (pinfunction "GPB3_4") (pintype "bidirectional"))
      (node (ref "U$5") (pin "21") (pinfunction "21_21") (pintype "bidirectional"))
    )
    (net (code "126") (name "XGPIO14") (class "Default")
      (node (ref "IC6") (pin "5") (pinfunction "GPB4_5") (pintype "bidirectional"))
      (node (ref "U$5") (pin "22") (pinfunction "22_22") (pintype "bidirectional"))
    )
    (net (code "127") (name "XGPIO15") (class "Default")
      (node (ref "IC6") (pin "6") (pinfunction "GPB5_6") (pintype "bidirectional"))
      (node (ref "U$5") (pin "23") (pinfunction "23_23") (pintype "bidirectional"))
    )
    (net (code "128") (name "XGPIO16") (class "Default")
      (node (ref "IC6") (pin "7") (pinfunction "GPB6_7") (pintype "bidirectional"))
      (node (ref "U$5") (pin "24") (pinfunction "24_24") (pintype "bidirectional"))
    )
    (net (code "129") (name "XGPIO17") (class "Default")
      (node (ref "IC6") (pin "8") (pinfunction "GPB7_8") (pintype "bidirectional"))
      (node (ref "U$5") (pin "25") (pinfunction "25_25") (pintype "bidirectional"))
    )
    (net (code "130") (name "unconnected-(IC3-3V3OUT-Pad17)") (class "Default")
      (node (ref "IC3") (pin "17") (pinfunction "3V3OUT_17") (pintype "output"))
    )
    (net (code "131") (name "unconnected-(IC3-CBUS2-Pad13)") (class "Default")
      (node (ref "IC3") (pin "13") (pinfunction "CBUS2_13") (pintype "bidirectional"))
    )
    (net (code "132") (name "unconnected-(IC3-CBUS3-Pad14)") (class "Default")
      (node (ref "IC3") (pin "14") (pinfunction "CBUS3_14") (pintype "bidirectional"))
    )
    (net (code "133") (name "unconnected-(IC3-CBUS4-Pad12)") (class "Default")
      (node (ref "IC3") (pin "12") (pinfunction "CBUS4_12") (pintype "bidirectional"))
    )
    (net (code "134") (name "unconnected-(IC3-OSCI-Pad27)") (class "Default")
      (node (ref "IC3") (pin "27") (pinfunction "OSCI_27") (pintype "input"))
    )
    (net (code "135") (name "unconnected-(IC3-OSCO-Pad28)") (class "Default")
      (node (ref "IC3") (pin "28") (pinfunction "OSCO_28") (pintype "output"))
    )
    (net (code "136") (name "unconnected-(IC3-~{CTS}-Pad11)") (class "Default")
      (node (ref "IC3") (pin "11") (pinfunction "~{CTS}_11") (pintype "input"))
    )
    (net (code "137") (name "unconnected-(IC3-~{DCD}-Pad10)") (class "Default")
      (node (ref "IC3") (pin "10") (pinfunction "~{DCD}_10") (pintype "input"))
    )
    (net (code "138") (name "unconnected-(IC3-~{DSR}-Pad9)") (class "Default")
      (node (ref "IC3") (pin "9") (pinfunction "~{DSR}_9") (pintype "input"))
    )
    (net (code "139") (name "unconnected-(IC3-~{DTR}-Pad2)") (class "Default")
      (node (ref "IC3") (pin "2") (pinfunction "~{DTR}_2") (pintype "output"))
    )
    (net (code "140") (name "unconnected-(IC3-~{RESET}-Pad19)") (class "Default")
      (node (ref "IC3") (pin "19") (pinfunction "~{RESET}_19") (pintype "input"))
    )
    (net (code "141") (name "unconnected-(IC3-~{RI}-Pad6)") (class "Default")
      (node (ref "IC3") (pin "6") (pinfunction "~{RI}_6") (pintype "input"))
    )
    (net (code "142") (name "unconnected-(IC3-~{RTS}-Pad3)") (class "Default")
      (node (ref "IC3") (pin "3") (pinfunction "~{RTS}_3") (pintype "output"))
    )
    (net (code "143") (name "unconnected-(IC4A-R2IN-Pad8)") (class "Default")
      (node (ref "IC4") (pin "8") (pinfunction "R2IN_8") (pintype "input"))
    )
    (net (code "144") (name "unconnected-(IC4A-R2OUT-Pad9)") (class "Default")
      (node (ref "IC4") (pin "9") (pinfunction "R2OUT_9") (pintype "output"))
    )
    (net (code "145") (name "unconnected-(IC4A-T2IN-Pad10)") (class "Default")
      (node (ref "IC4") (pin "10") (pinfunction "T2IN_10") (pintype "input"))
    )
    (net (code "146") (name "unconnected-(IC4A-T2OUT-Pad7)") (class "Default")
      (node (ref "IC4") (pin "7") (pinfunction "T2OUT_7") (pintype "output"))
    )
    (net (code "147") (name "unconnected-(IC5-INTA-Pad20)") (class "Default")
      (node (ref "IC5") (pin "20") (pinfunction "INTA_20") (pintype "output"))
    )
    (net (code "148") (name "unconnected-(IC5-INTB-Pad19)") (class "Default")
      (node (ref "IC5") (pin "19") (pinfunction "INTB_19") (pintype "output"))
    )
    (net (code "149") (name "unconnected-(IC6-INTA-Pad20)") (class "Default")
      (node (ref "IC6") (pin "20") (pinfunction "INTA_20") (pintype "output"))
    )
    (net (code "150") (name "unconnected-(IC6-INTB-Pad19)") (class "Default")
      (node (ref "IC6") (pin "19") (pinfunction "INTB_19") (pintype "output"))
    )
    (net (code "151") (name "unconnected-(U$1-Pad1)") (class "Default")
      (node (ref "U$1") (pin "1") (pinfunction "1_1") (pintype "bidirectional"))
    )
    (net (code "152") (name "unconnected-(U$1-Pad2)") (class "Default")
      (node (ref "U$1") (pin "2") (pinfunction "2_2") (pintype "bidirectional"))
    )
    (net (code "153") (name "unconnected-(U$1-Pad3)") (class "Default")
      (node (ref "U$1") (pin "3") (pinfunction "3_3") (pintype "bidirectional"))
    )
    (net (code "154") (name "unconnected-(U$1-Pad4)") (class "Default")
      (node (ref "U$1") (pin "4") (pinfunction "4_4") (pintype "bidirectional"))
    )
    (net (code "155") (name "unconnected-(U$1-Pad5)") (class "Default")
      (node (ref "U$1") (pin "5") (pinfunction "5_5") (pintype "bidirectional"))
    )
    (net (code "156") (name "unconnected-(U$1-Pad6)") (class "Default")
      (node (ref "U$1") (pin "6") (pinfunction "6_6") (pintype "bidirectional"))
    )
    (net (code "157") (name "unconnected-(U$1-Pad7)") (class "Default")
      (node (ref "U$1") (pin "7") (pinfunction "7_7") (pintype "bidirectional"))
    )
    (net (code "158") (name "unconnected-(U$1-Pad8)") (class "Default")
      (node (ref "U$1") (pin "8") (pinfunction "8_8") (pintype "bidirectional"))
    )
    (net (code "159") (name "unconnected-(U$1-Pad9)") (class "Default")
      (node (ref "U$1") (pin "9") (pinfunction "9_9") (pintype "bidirectional"))
    )
    (net (code "160") (name "unconnected-(U$1-Pad10)") (class "Default")
      (node (ref "U$1") (pin "10") (pinfunction "10_10") (pintype "bidirectional"))
    )
    (net (code "161") (name "unconnected-(U$1-Pad11)") (class "Default")
      (node (ref "U$1") (pin "11") (pinfunction "11_11") (pintype "bidirectional"))
    )
    (net (code "162") (name "unconnected-(U$1-Pad12)") (class "Default")
      (node (ref "U$1") (pin "12") (pinfunction "12_12") (pintype "bidirectional"))
    )
    (net (code "163") (name "unconnected-(U$1-Pad13)") (class "Default")
      (node (ref "U$1") (pin "13") (pinfunction "13_13") (pintype "bidirectional"))
    )
    (net (code "164") (name "unconnected-(U$1-Pad14)") (class "Default")
      (node (ref "U$1") (pin "14") (pinfunction "14_14") (pintype "bidirectional"))
    )
    (net (code "165") (name "unconnected-(U$1-Pad15)") (class "Default")
      (node (ref "U$1") (pin "15") (pinfunction "15_15") (pintype "bidirectional"))
    )
    (net (code "166") (name "unconnected-(U$1-Pad16)") (class "Default")
      (node (ref "U$1") (pin "16") (pinfunction "16_16") (pintype "bidirectional"))
    )
    (net (code "167") (name "unconnected-(U$1-Pad17)") (class "Default")
      (node (ref "U$1") (pin "17") (pinfunction "17_17") (pintype "bidirectional"))
    )
    (net (code "168") (name "unconnected-(U$1-Pad18)") (class "Default")
      (node (ref "U$1") (pin "18") (pinfunction "18_18") (pintype "bidirectional"))
    )
    (net (code "169") (name "unconnected-(U$1-Pad19)") (class "Default")
      (node (ref "U$1") (pin "19") (pinfunction "19_19") (pintype "bidirectional"))
    )
    (net (code "170") (name "unconnected-(U$1-Pad20)") (class "Default")
      (node (ref "U$1") (pin "20") (pinfunction "20_20") (pintype "bidirectional"))
    )
    (net (code "171") (name "unconnected-(U$1-Pad21)") (class "Default")
      (node (ref "U$1") (pin "21") (pinfunction "21_21") (pintype "bidirectional"))
    )
    (net (code "172") (name "unconnected-(U$1-Pad35)") (class "Default")
      (node (ref "U$1") (pin "35") (pinfunction "35_35") (pintype "bidirectional"))
    )
    (net (code "173") (name "unconnected-(U$1-Pad47)") (class "Default")
      (node (ref "U$1") (pin "47") (pinfunction "47_47") (pintype "bidirectional"))
    )
    (net (code "174") (name "unconnected-(U$1-Pad48)") (class "Default")
      (node (ref "U$1") (pin "48") (pinfunction "48_48") (pintype "bidirectional"))
    )
    (net (code "175") (name "unconnected-(U$1-Pad49)") (class "Default")
      (node (ref "U$1") (pin "49") (pinfunction "49_49") (pintype "bidirectional"))
    )
    (net (code "176") (name "unconnected-(U$1-Pad57)") (class "Default")
      (node (ref "U$1") (pin "57") (pinfunction "57_57") (pintype "bidirectional"))
    )
    (net (code "177") (name "unconnected-(U$1-Pad58)") (class "Default")
      (node (ref "U$1") (pin "58") (pinfunction "58_58") (pintype "bidirectional"))
    )
    (net (code "178") (name "unconnected-(U$1-Pad59)") (class "Default")
      (node (ref "U$1") (pin "59") (pinfunction "59_59") (pintype "bidirectional"))
    )
    (net (code "179") (name "unconnected-(U$1-Pad60)") (class "Default")
      (node (ref "U$1") (pin "60") (pinfunction "60_60") (pintype "bidirectional"))
    )
    (net (code "180") (name "unconnected-(U$1-Pad61)") (class "Default")
      (node (ref "U$1") (pin "61") (pinfunction "61_61") (pintype "bidirectional"))
    )
    (net (code "181") (name "unconnected-(U$1-Pad64)") (class "Default")
      (node (ref "U$1") (pin "64") (pinfunction "64_64") (pintype "bidirectional"))
    )
    (net (code "182") (name "unconnected-(U$1-Pad65)") (class "Default")
      (node (ref "U$1") (pin "65") (pinfunction "65_65") (pintype "bidirectional"))
    )
    (net (code "183") (name "unconnected-(U$1-Pad66)") (class "Default")
      (node (ref "U$1") (pin "66") (pinfunction "66_66") (pintype "bidirectional"))
    )
    (net (code "184") (name "unconnected-(U$1-Pad67)") (class "Default")
      (node (ref "U$1") (pin "67") (pinfunction "67_67") (pintype "bidirectional"))
    )
    (net (code "185") (name "unconnected-(U$1-Pad68)") (class "Default")
      (node (ref "U$1") (pin "68") (pinfunction "68_68") (pintype "bidirectional"))
    )
    (net (code "186") (name "unconnected-(U$1-Pad72)") (class "Default")
      (node (ref "U$1") (pin "72") (pinfunction "72_72") (pintype "bidirectional"))
    )
    (net (code "187") (name "unconnected-(U$1-PadP1)") (class "Default")
      (node (ref "U$1") (pin "P1") (pinfunction "P1_P1") (pintype "bidirectional"))
    )
    (net (code "188") (name "unconnected-(U$1-PadP8)") (class "Default")
      (node (ref "U$1") (pin "P8") (pinfunction "P8_P8") (pintype "bidirectional"))
    )
    (net (code "189") (name "unconnected-(U$1-PadP9)") (class "Default")
      (node (ref "U$1") (pin "P9") (pinfunction "P9_P9") (pintype "bidirectional"))
    )
    (net (code "190") (name "unconnected-(U$1-PadP17)") (class "Default")
      (node (ref "U$1") (pin "P17") (pinfunction "P17_P17") (pintype "bidirectional"))
    )
    (net (code "191") (name "unconnected-(U$1-PadP18)") (class "Default")
      (node (ref "U$1") (pin "P18") (pinfunction "P18_P18") (pintype "bidirectional"))
    )
    (net (code "192") (name "unconnected-(U$1-PadP19)") (class "Default")
      (node (ref "U$1") (pin "P19") (pinfunction "P19_P19") (pintype "bidirectional"))
    )
    (net (code "193") (name "unconnected-(U$1-PadP20)") (class "Default")
      (node (ref "U$1") (pin "P20") (pinfunction "P20_P20") (pintype "bidirectional"))
    )
    (net (code "194") (name "unconnected-(U$1-PadP21)") (class "Default")
      (node (ref "U$1") (pin "P21") (pinfunction "P21_P21") (pintype "bidirectional"))
    )
    (net (code "195") (name "unconnected-(U$1-PadP22)") (class "Default")
      (node (ref "U$1") (pin "P22") (pinfunction "P22_P22") (pintype "bidirectional"))
    )
    (net (code "196") (name "unconnected-(U$1-PadP23)") (class "Default")
      (node (ref "U$1") (pin "P23") (pinfunction "P23_P23") (pintype "bidirectional"))
    )
    (net (code "197") (name "unconnected-(U$1-PadP24)") (class "Default")
      (node (ref "U$1") (pin "P24") (pinfunction "P24_P24") (pintype "bidirectional"))
    )
    (net (code "198") (name "unconnected-(U$1-PadP25)") (class "Default")
      (node (ref "U$1") (pin "P25") (pinfunction "P25_P25") (pintype "bidirectional"))
    )
    (net (code "199") (name "unconnected-(U$1-PadP26)") (class "Default")
      (node (ref "U$1") (pin "P26") (pinfunction "P26_P26") (pintype "bidirectional"))
    )
    (net (code "200") (name "unconnected-(U$1-PadP27)") (class "Default")
      (node (ref "U$1") (pin "P27") (pinfunction "P27_P27") (pintype "bidirectional"))
    )
    (net (code "201") (name "unconnected-(U$1-PadP28)") (class "Default")
      (node (ref "U$1") (pin "P28") (pinfunction "P28_P28") (pintype "bidirectional"))
    )
    (net (code "202") (name "unconnected-(U$1-PadP29)") (class "Default")
      (node (ref "U$1") (pin "P29") (pinfunction "P29_P29") (pintype "bidirectional"))
    )
    (net (code "203") (name "unconnected-(U$1-PadP30)") (class "Default")
      (node (ref "U$1") (pin "P30") (pinfunction "P30_P30") (pintype "bidirectional"))
    )
    (net (code "204") (name "unconnected-(U$1-PadP31)") (class "Default")
      (node (ref "U$1") (pin "P31") (pinfunction "P31_P31") (pintype "bidirectional"))
    )
    (net (code "205") (name "unconnected-(U$1-PadP32)") (class "Default")
      (node (ref "U$1") (pin "P32") (pinfunction "P32_P32") (pintype "bidirectional"))
    )
    (net (code "206") (name "unconnected-(U$1-PadP33)") (class "Default")
      (node (ref "U$1") (pin "P33") (pinfunction "P33_P33") (pintype "bidirectional"))
    )
    (net (code "207") (name "unconnected-(U$1-PadP34)") (class "Default")
      (node (ref "U$1") (pin "P34") (pinfunction "P34_P34") (pintype "bidirectional"))
    )
    (net (code "208") (name "unconnected-(U$1-PadP35)") (class "Default")
      (node (ref "U$1") (pin "P35") (pinfunction "P35_P35") (pintype "bidirectional"))
    )
    (net (code "209") (name "unconnected-(U$1-PadP36)") (class "Default")
      (node (ref "U$1") (pin "P36") (pinfunction "P36_P36") (pintype "bidirectional"))
    )
    (net (code "210") (name "unconnected-(U$1-PadP37)") (class "Default")
      (node (ref "U$1") (pin "P37") (pinfunction "P37_P37") (pintype "bidirectional"))
    )
    (net (code "211") (name "unconnected-(U$1-PadP38)") (class "Default")
      (node (ref "U$1") (pin "P38") (pinfunction "P38_P38") (pintype "bidirectional"))
    )
    (net (code "212") (name "unconnected-(U$1-PadP39)") (class "Default")
      (node (ref "U$1") (pin "P39") (pinfunction "P39_P39") (pintype "bidirectional"))
    )
    (net (code "213") (name "unconnected-(U$1-PadP40)") (class "Default")
      (node (ref "U$1") (pin "P40") (pinfunction "P40_P40") (pintype "bidirectional"))
    )
    (net (code "214") (name "unconnected-(U$1-PadP41)") (class "Default")
      (node (ref "U$1") (pin "P41") (pinfunction "P41_P41") (pintype "bidirectional"))
    )
    (net (code "215") (name "unconnected-(U$1-PadP42)") (class "Default")
      (node (ref "U$1") (pin "P42") (pinfunction "P42_P42") (pintype "bidirectional"))
    )
    (net (code "216") (name "unconnected-(U$1-PadP43)") (class "Default")
      (node (ref "U$1") (pin "P43") (pinfunction "P43_P43") (pintype "bidirectional"))
    )
    (net (code "217") (name "unconnected-(U$1-PadP44)") (class "Default")
      (node (ref "U$1") (pin "P44") (pinfunction "P44_P44") (pintype "bidirectional"))
    )
    (net (code "218") (name "unconnected-(U$1-PadP45)") (class "Default")
      (node (ref "U$1") (pin "P45") (pinfunction "P45_P45") (pintype "bidirectional"))
    )
    (net (code "219") (name "unconnected-(U$1-PadP46)") (class "Default")
      (node (ref "U$1") (pin "P46") (pinfunction "P46_P46") (pintype "bidirectional"))
    )
    (net (code "220") (name "unconnected-(U$1-PadP47)") (class "Default")
      (node (ref "U$1") (pin "P47") (pinfunction "P47_P47") (pintype "bidirectional"))
    )
    (net (code "221") (name "unconnected-(U$1-PadP48)") (class "Default")
      (node (ref "U$1") (pin "P48") (pinfunction "P48_P48") (pintype "bidirectional"))
    )
    (net (code "222") (name "unconnected-(U$1-PadP49)") (class "Default")
      (node (ref "U$1") (pin "P49") (pinfunction "P49_P49") (pintype "bidirectional"))
    )
    (net (code "223") (name "unconnected-(U$1-PadP50)") (class "Default")
      (node (ref "U$1") (pin "P50") (pinfunction "P50_P50") (pintype "bidirectional"))
    )
    (net (code "224") (name "unconnected-(U$1-PadP51)") (class "Default")
      (node (ref "U$1") (pin "P51") (pinfunction "P51_P51") (pintype "bidirectional"))
    )
    (net (code "225") (name "unconnected-(U$1-PadP52)") (class "Default")
      (node (ref "U$1") (pin "P52") (pinfunction "P52_P52") (pintype "bidirectional"))
    )
    (net (code "226") (name "unconnected-(U$1-PadP53)") (class "Default")
      (node (ref "U$1") (pin "P53") (pinfunction "P53_P53") (pintype "bidirectional"))
    )
    (net (code "227") (name "unconnected-(U$1-PadP54)") (class "Default")
      (node (ref "U$1") (pin "P54") (pinfunction "P54_P54") (pintype "bidirectional"))
    )
    (net (code "228") (name "unconnected-(U$1-PadP55)") (class "Default")
      (node (ref "U$1") (pin "P55") (pinfunction "P55_P55") (pintype "bidirectional"))
    )
    (net (code "229") (name "unconnected-(U$1-PadP57)") (class "Default")
      (node (ref "U$1") (pin "P57") (pinfunction "P57_P57") (pintype "bidirectional"))
    )
    (net (code "230") (name "unconnected-(U$1-PadP58)") (class "Default")
      (node (ref "U$1") (pin "P58") (pinfunction "P58_P58") (pintype "bidirectional"))
    )
    (net (code "231") (name "unconnected-(U$1-PadP59)") (class "Default")
      (node (ref "U$1") (pin "P59") (pinfunction "P59_P59") (pintype "bidirectional"))
    )
    (net (code "232") (name "unconnected-(U$1-PadP60)") (class "Default")
      (node (ref "U$1") (pin "P60") (pinfunction "P60_P60") (pintype "bidirectional"))
    )
    (net (code "233") (name "unconnected-(U$1-PadP61)") (class "Default")
      (node (ref "U$1") (pin "P61") (pinfunction "P61_P61") (pintype "bidirectional"))
    )
    (net (code "234") (name "unconnected-(U$1-PadP62)") (class "Default")
      (node (ref "U$1") (pin "P62") (pinfunction "P62_P62") (pintype "bidirectional"))
    )
    (net (code "235") (name "unconnected-(U$1-PadP63)") (class "Default")
      (node (ref "U$1") (pin "P63") (pinfunction "P63_P63") (pintype "bidirectional"))
    )
    (net (code "236") (name "unconnected-(U$1-PadP64)") (class "Default")
      (node (ref "U$1") (pin "P64") (pinfunction "P64_P64") (pintype "bidirectional"))
    )
    (net (code "237") (name "unconnected-(U$1-PadP65)") (class "Default")
      (node (ref "U$1") (pin "P65") (pinfunction "P65_P65") (pintype "bidirectional"))
    )
    (net (code "238") (name "unconnected-(U$1-PadP66)") (class "Default")
      (node (ref "U$1") (pin "P66") (pinfunction "P66_P66") (pintype "bidirectional"))
    )
    (net (code "239") (name "unconnected-(U$1-PadP67)") (class "Default")
      (node (ref "U$1") (pin "P67") (pinfunction "P67_P67") (pintype "bidirectional"))
    )
    (net (code "240") (name "unconnected-(U$1-PadP68)") (class "Default")
      (node (ref "U$1") (pin "P68") (pinfunction "P68_P68") (pintype "bidirectional"))
    )
    (net (code "241") (name "unconnected-(U$1-PadP69)") (class "Default")
      (node (ref "U$1") (pin "P69") (pinfunction "P69_P69") (pintype "bidirectional"))
    )
    (net (code "242") (name "unconnected-(U$1-PadP70)") (class "Default")
      (node (ref "U$1") (pin "P70") (pinfunction "P70_P70") (pintype "bidirectional"))
    )
    (net (code "243") (name "unconnected-(U$1-PadP71)") (class "Default")
      (node (ref "U$1") (pin "P71") (pinfunction "P71_P71") (pintype "bidirectional"))
    )
    (net (code "244") (name "unconnected-(U$1-PadP72)") (class "Default")
      (node (ref "U$1") (pin "P72") (pinfunction "P72_P72") (pintype "bidirectional"))
    )
    (net (code "245") (name "unconnected-(U$1-PadP73)") (class "Default")
      (node (ref "U$1") (pin "P73") (pinfunction "P73_P73") (pintype "bidirectional"))
    )
    (net (code "246") (name "unconnected-(U$1-PadP74)") (class "Default")
      (node (ref "U$1") (pin "P74") (pinfunction "P74_P74") (pintype "bidirectional"))
    )
    (net (code "247") (name "unconnected-(U$2-5-2-Pad4)") (class "Default")
      (node (ref "U$2") (pin "4") (pinfunction "5-2_4") (pintype "bidirectional"))
    )
    (net (code "248") (name "unconnected-(U$2-PCM-Pad12)") (class "Default")
      (node (ref "U$2") (pin "12") (pinfunction "PCM_12") (pintype "bidirectional"))
    )
    (net (code "249") (name "unconnected-(U$2-SC-Pad28)") (class "Default")
      (node (ref "U$2") (pin "28") (pinfunction "SC_28") (pintype "bidirectional"))
    )
    (net (code "250") (name "unconnected-(U$2-SD-Pad27)") (class "Default")
      (node (ref "U$2") (pin "27") (pinfunction "SD_27") (pintype "bidirectional"))
    )
    (net (code "251") (name "unconnected-(U4-OUT-Pad4)") (class "Default")
      (node (ref "U4") (pin "4") (pinfunction "OUT_4") (pintype "output"))
    )
  )
)
